# TMC2660-test-with-grbl2.net
KiCad netlist of a schematic drawn in EAGLE
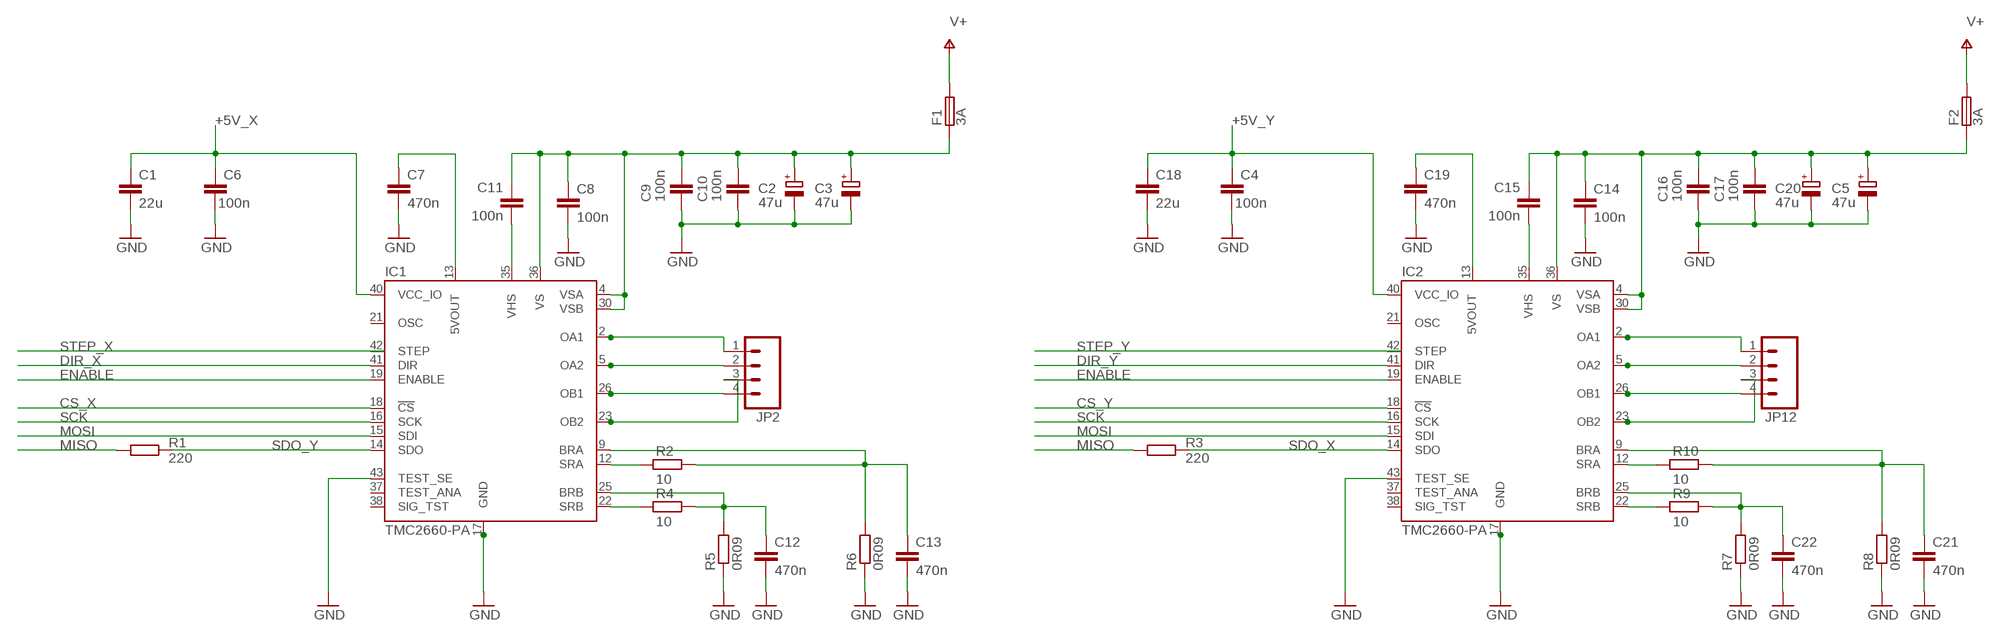
[diagram p0: schematic, sheet 1, part 1 of 2]
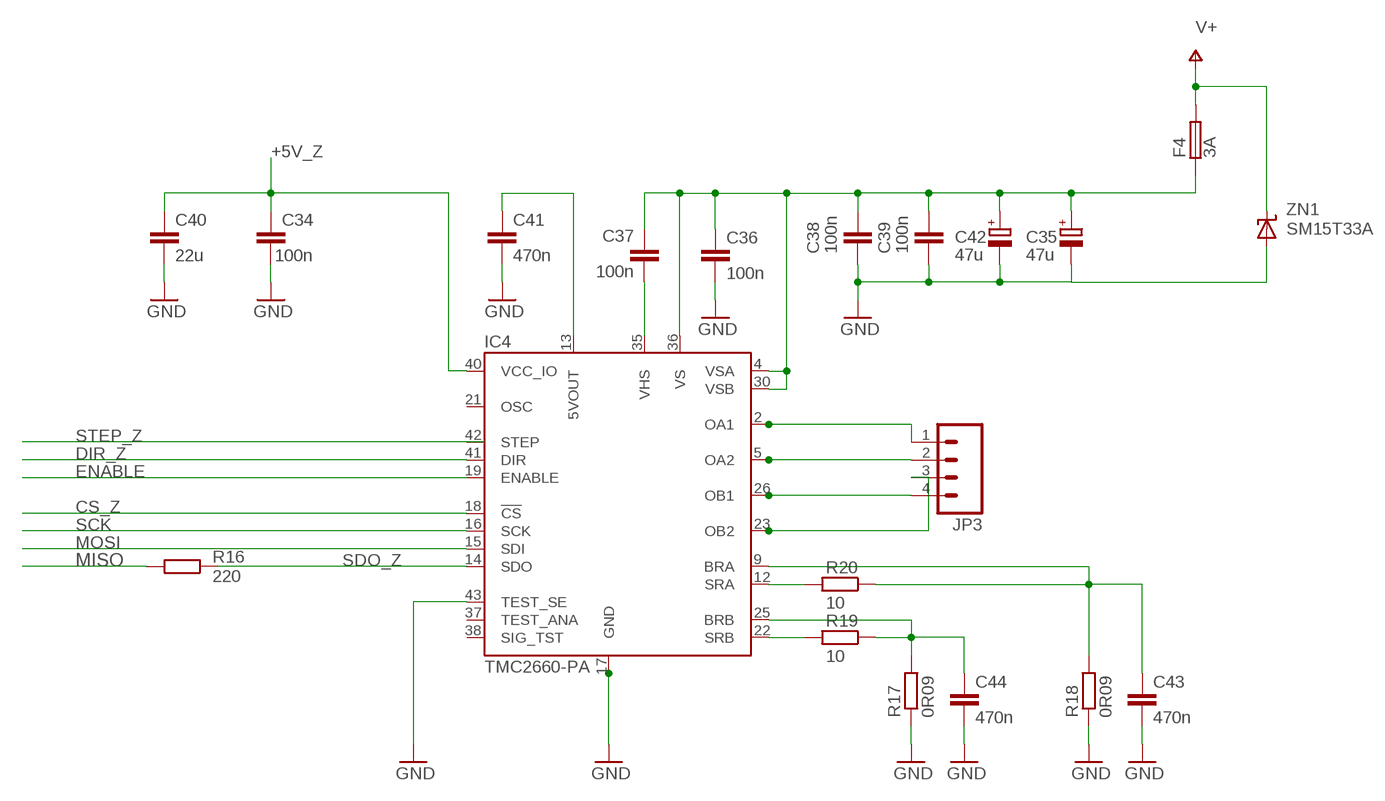
[diagram p1: schematic, sheet 1, part 2 of 2]
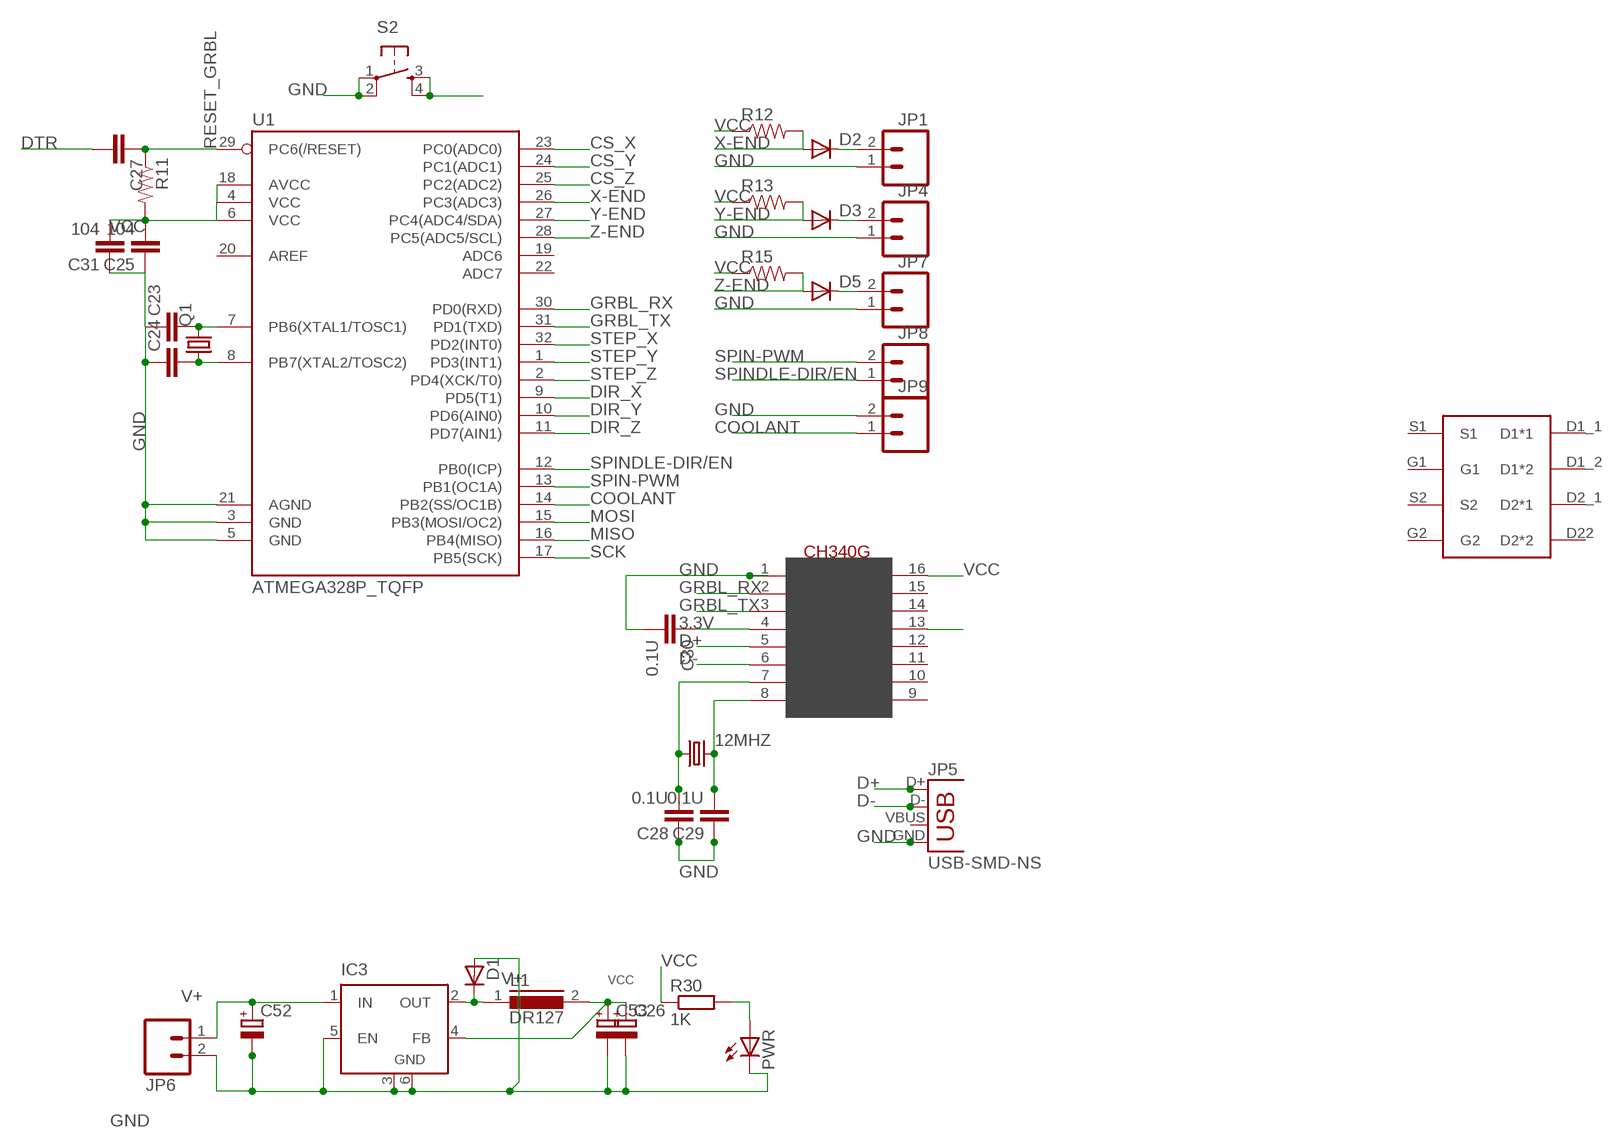
[diagram p2: schematic, sheet 2]

(export (version "E")
  (design (tool "Eeschema 10.0.6"))
  (components
    (comp (ref "12MHZ")
      (value "CRYSTALHC49UP")
      (footprint "eagle-import:HC49UP")
      (libsource (lib "eagle-import") (part "crystal_CRYSTALHC49UP"))
    )
    (comp (ref "C23")
      (value "CAP1206")
      (footprint "eagle-import:1206")
      (libsource (lib "eagle-import") (part "CAP1206"))
    )
    (comp (ref "C24")
      (value "CAP1206")
      (footprint "eagle-import:1206")
      (libsource (lib "eagle-import") (part "CAP1206"))
    )
    (comp (ref "C25")
      (value "104")
      (footprint "eagle-import:1206")
      (libsource (lib "eagle-import") (part "CAP1206"))
    )
    (comp (ref "C26")
      (value "CPOL-EUE2.5-6")
      (footprint "eagle-import:E2,5-6")
      (libsource (lib "eagle-import") (part "resistor_CPOL-EUE2.5-6"))
    )
    (comp (ref "C27")
      (value "CAP1206")
      (footprint "eagle-import:1206")
      (libsource (lib "eagle-import") (part "CAP1206"))
    )
    (comp (ref "C28")
      (value "0.1U")
      (footprint "eagle-import:C1206")
      (libsource (lib "eagle-import") (part "C-EUC1206"))
    )
    (comp (ref "C29")
      (value "0.1U")
      (footprint "eagle-import:C1206")
      (libsource (lib "eagle-import") (part "C-EUC1206"))
    )
    (comp (ref "C30")
      (value "0.1U")
      (footprint "eagle-import:C1206")
      (libsource (lib "eagle-import") (part "C-EUC1206"))
    )
    (comp (ref "C31")
      (value "104")
      (footprint "eagle-import:1206")
      (libsource (lib "eagle-import") (part "CAP1206"))
    )
    (comp (ref "C52")
      (value "CPOL-EUE5-8.5")
      (footprint "eagle-import:E5-8,5")
      (libsource (lib "eagle-import") (part "resistor_CPOL-EUE5-8.5"))
    )
    (comp (ref "C53")
      (value "CPOL-EUE5-8.5")
      (footprint "eagle-import:E5-8,5")
      (libsource (lib "eagle-import") (part "resistor_CPOL-EUE5-8.5"))
    )
    (comp (ref "D1")
      (value "D-SOD-80")
      (footprint "eagle-import:SOD80")
      (libsource (lib "eagle-import") (part "D-SOD-80"))
    )
    (comp (ref "D2")
      (value "DIODESMB")
      (footprint "eagle-import:SMB-DIODE")
      (libsource (lib "eagle-import") (part "DIODESMB"))
    )
    (comp (ref "D3")
      (value "DIODESMB")
      (footprint "eagle-import:SMB-DIODE")
      (libsource (lib "eagle-import") (part "DIODESMB"))
    )
    (comp (ref "D5")
      (value "DIODESMB")
      (footprint "eagle-import:SMB-DIODE")
      (libsource (lib "eagle-import") (part "DIODESMB"))
    )
    (comp (ref "IC3")
      (value "LM2596S")
      (footprint "eagle-import:TO263-5")
      (libsource (lib "eagle-import") (part "LM2596S"))
    )
    (comp (ref "JP1")
      (value "M023.5MM")
      (footprint "eagle-import:SCREWTERMINAL-3.5MM-2")
      (libsource (lib "eagle-import") (part "M023.5MM"))
    )
    (comp (ref "JP4")
      (value "M023.5MM")
      (footprint "eagle-import:SCREWTERMINAL-3.5MM-2")
      (libsource (lib "eagle-import") (part "M023.5MM"))
    )
    (comp (ref "JP5")
      (value "USB-SMD-NS")
      (footprint "eagle-import:USB-MINIB-NOSTOP")
      (libsource (lib "eagle-import") (part "USB-SMD-NS"))
    )
    (comp (ref "JP6")
      (value "M023.5MM")
      (footprint "eagle-import:SCREWTERMINAL-3.5MM-2")
      (libsource (lib "eagle-import") (part "M023.5MM"))
    )
    (comp (ref "JP7")
      (value "M023.5MM")
      (footprint "eagle-import:SCREWTERMINAL-3.5MM-2")
      (libsource (lib "eagle-import") (part "M023.5MM"))
    )
    (comp (ref "JP8")
      (value "M023.5MM")
      (footprint "eagle-import:SCREWTERMINAL-3.5MM-2")
      (libsource (lib "eagle-import") (part "M023.5MM"))
    )
    (comp (ref "JP9")
      (value "M023.5MM")
      (footprint "eagle-import:SCREWTERMINAL-3.5MM-2")
      (libsource (lib "eagle-import") (part "M023.5MM"))
    )
    (comp (ref "L1")
      (value "DR127")
      (footprint "eagle-import:DR127")
      (libsource (lib "eagle-import") (part "DR127"))
    )
    (comp (ref "PWR")
      (value "LEDCHIPLED_1206")
      (footprint "eagle-import:CHIPLED_1206")
      (libsource (lib "eagle-import") (part "LEDCHIPLED_1206"))
    )
    (comp (ref "Q1")
      (value "CRYSTALHC49UP")
      (footprint "eagle-import:HC49UP")
      (libsource (lib "eagle-import") (part "CRYSTALHC49UP"))
    )
    (comp (ref "R11")
      (value "RESISTOR1206")
      (footprint "eagle-import:1206")
      (libsource (lib "eagle-import") (part "RESISTOR1206"))
    )
    (comp (ref "R12")
      (value "RESISTOR1206")
      (footprint "eagle-import:1206")
      (libsource (lib "eagle-import") (part "RESISTOR1206"))
    )
    (comp (ref "R13")
      (value "RESISTOR1206")
      (footprint "eagle-import:1206")
      (libsource (lib "eagle-import") (part "RESISTOR1206"))
    )
    (comp (ref "R15")
      (value "RESISTOR1206")
      (footprint "eagle-import:1206")
      (libsource (lib "eagle-import") (part "RESISTOR1206"))
    )
    (comp (ref "R30")
      (value "1K")
      (footprint "eagle-import:M1206")
      (libsource (lib "eagle-import") (part "R-EU_M1206"))
    )
    (comp (ref "S2")
      (value "TAC_SWITCHSMD")
      (footprint "eagle-import:TACTILE_SWITCH_SMD")
      (libsource (lib "eagle-import") (part "TAC_SWITCHSMD"))
    )
    (comp (ref "U$3")
      (value "CSD88537ND")
      (footprint "eagle-import:CSD88537ND")
      (libsource (lib "eagle-import") (part "CSD88537ND"))
    )
    (comp (ref "U$4")
      (value "CH340G")
      (footprint "eagle-import:SOIC16")
      (libsource (lib "eagle-import") (part "CH340G"))
    )
    (comp (ref "U1")
      (value "ATMEGA328P_TQFP")
      (footprint "eagle-import:TQFP32-08")
      (libsource (lib "eagle-import") (part "ATMEGA328P_TQFP"))
    )
    (comp (ref "C1")
      (value "22u")
      (footprint "eagle-import:C1206")
      (fields (field (name "MANUFACTURER") "Taiyo Yuden") (field (name "VOLTAGE") "6.3V"))
      (libsource (lib "eagle-import") (part "C-EUC1206"))
    )
    (comp (ref "C2")
      (value "47u")
      (footprint "eagle-import:E5-8,5")
      (fields (field (name "MANUFACTURER") "PANASONIC") (field (name "VOLTAGE") "50V"))
      (libsource (lib "eagle-import") (part "CPOL-EUE5-8.5"))
    )
    (comp (ref "C3")
      (value "47u")
      (footprint "eagle-import:E5-8,5")
      (fields (field (name "MANUFACTURER") "PANASONIC") (field (name "VOLTAGE") "50V"))
      (libsource (lib "eagle-import") (part "CPOL-EUE5-8.5"))
    )
    (comp (ref "C4")
      (value "100n")
      (footprint "eagle-import:C1206K")
      (fields (field (name "MANUFACTURER") "Kemet") (field (name "VOLTAGE") "25V"))
      (libsource (lib "eagle-import") (part "C-EUC1206K"))
    )
    (comp (ref "C5")
      (value "47u")
      (footprint "eagle-import:E5-8,5")
      (fields (field (name "MANUFACTURER") "PANASONIC") (field (name "VOLTAGE") "50V"))
      (libsource (lib "eagle-import") (part "CPOL-EUE5-8.5"))
    )
    (comp (ref "C6")
      (value "100n")
      (footprint "eagle-import:C1206K")
      (fields (field (name "MANUFACTURER") "Kemet") (field (name "VOLTAGE") "25V"))
      (libsource (lib "eagle-import") (part "C-EUC1206K"))
    )
    (comp (ref "C7")
      (value "470n")
      (footprint "eagle-import:0805-WIDE")
      (fields (field (name "MANUFACTURER") "Vishay") (field (name "VOLTAGE") "10V"))
      (libsource (lib "eagle-import") (part "C-0805W"))
    )
    (comp (ref "C8")
      (value "100n")
      (footprint "eagle-import:C0603K")
      (fields (field (name "MANUFACTURER") "Kemet") (field (name "VOLTAGE") "50V"))
      (libsource (lib "eagle-import") (part "C-EUC0603K"))
    )
    (comp (ref "C9")
      (value "100n")
      (footprint "eagle-import:C0603K")
      (fields (field (name "MANUFACTURER") "Kemet") (field (name "VOLTAGE") "50V"))
      (libsource (lib "eagle-import") (part "C-EUC0603K"))
    )
    (comp (ref "C10")
      (value "100n")
      (footprint "eagle-import:C0603K")
      (fields (field (name "MANUFACTURER") "Kemet") (field (name "VOLTAGE") "50V"))
      (libsource (lib "eagle-import") (part "C-EUC0603K"))
    )
    (comp (ref "C11")
      (value "100n")
      (footprint "eagle-import:C0603K")
      (fields (field (name "MANUFACTURER") "Kemet") (field (name "VOLTAGE") "50V"))
      (libsource (lib "eagle-import") (part "C-EUC0603K"))
    )
    (comp (ref "C12")
      (value "470n")
      (footprint "eagle-import:0805-WIDE")
      (fields (field (name "MANUFACTURER") "Vishay") (field (name "VOLTAGE") "10V"))
      (libsource (lib "eagle-import") (part "C-0805W"))
    )
    (comp (ref "C13")
      (value "470n")
      (footprint "eagle-import:0805-WIDE")
      (fields (field (name "MANUFACTURER") "Vishay") (field (name "VOLTAGE") "10V"))
      (libsource (lib "eagle-import") (part "C-0805W"))
    )
    (comp (ref "C14")
      (value "100n")
      (footprint "eagle-import:C0603K")
      (fields (field (name "MANUFACTURER") "Kemet") (field (name "VOLTAGE") "50V"))
      (libsource (lib "eagle-import") (part "C-EUC0603K"))
    )
    (comp (ref "C15")
      (value "100n")
      (footprint "eagle-import:C0603K")
      (fields (field (name "MANUFACTURER") "Kemet") (field (name "VOLTAGE") "50V"))
      (libsource (lib "eagle-import") (part "C-EUC0603K"))
    )
    (comp (ref "C16")
      (value "100n")
      (footprint "eagle-import:C0603K")
      (fields (field (name "MANUFACTURER") "Kemet") (field (name "VOLTAGE") "50V"))
      (libsource (lib "eagle-import") (part "C-EUC0603K"))
    )
    (comp (ref "C17")
      (value "100n")
      (footprint "eagle-import:C0603K")
      (fields (field (name "MANUFACTURER") "Kemet") (field (name "VOLTAGE") "50V"))
      (libsource (lib "eagle-import") (part "C-EUC0603K"))
    )
    (comp (ref "C18")
      (value "22u")
      (footprint "eagle-import:C1206")
      (fields (field (name "MANUFACTURER") "Taiyo Yuden") (field (name "VOLTAGE") "6.3V"))
      (libsource (lib "eagle-import") (part "C-EUC1206"))
    )
    (comp (ref "C19")
      (value "470n")
      (footprint "eagle-import:0805-WIDE")
      (fields (field (name "MANUFACTURER") "Vishay") (field (name "VOLTAGE") "10V"))
      (libsource (lib "eagle-import") (part "C-0805W"))
    )
    (comp (ref "C20")
      (value "47u")
      (footprint "eagle-import:E5-8,5")
      (fields (field (name "MANUFACTURER") "PANASONIC") (field (name "VOLTAGE") "50V"))
      (libsource (lib "eagle-import") (part "CPOL-EUE5-8.5"))
    )
    (comp (ref "C21")
      (value "470n")
      (footprint "eagle-import:0805-WIDE")
      (fields (field (name "MANUFACTURER") "Vishay") (field (name "VOLTAGE") "10V"))
      (libsource (lib "eagle-import") (part "C-0805W"))
    )
    (comp (ref "C22")
      (value "470n")
      (footprint "eagle-import:0805-WIDE")
      (fields (field (name "MANUFACTURER") "Vishay") (field (name "VOLTAGE") "10V"))
      (libsource (lib "eagle-import") (part "C-0805W"))
    )
    (comp (ref "C34")
      (value "100n")
      (footprint "eagle-import:C1206K")
      (fields (field (name "MANUFACTURER") "Kemet") (field (name "VOLTAGE") "25V"))
      (libsource (lib "eagle-import") (part "C-EUC1206K"))
    )
    (comp (ref "C35")
      (value "47u")
      (footprint "eagle-import:E5-8,5")
      (fields (field (name "MANUFACTURER") "PANASONIC") (field (name "VOLTAGE") "50V"))
      (libsource (lib "eagle-import") (part "CPOL-EUE5-8.5"))
    )
    (comp (ref "C36")
      (value "100n")
      (footprint "eagle-import:C0603K")
      (fields (field (name "MANUFACTURER") "Kemet") (field (name "VOLTAGE") "50V"))
      (libsource (lib "eagle-import") (part "C-EUC0603K"))
    )
    (comp (ref "C37")
      (value "100n")
      (footprint "eagle-import:C0603K")
      (fields (field (name "MANUFACTURER") "Kemet") (field (name "VOLTAGE") "50V"))
      (libsource (lib "eagle-import") (part "C-EUC0603K"))
    )
    (comp (ref "C38")
      (value "100n")
      (footprint "eagle-import:C0603K")
      (fields (field (name "MANUFACTURER") "Kemet") (field (name "VOLTAGE") "50V"))
      (libsource (lib "eagle-import") (part "C-EUC0603K"))
    )
    (comp (ref "C39")
      (value "100n")
      (footprint "eagle-import:C0603K")
      (fields (field (name "MANUFACTURER") "Kemet") (field (name "VOLTAGE") "50V"))
      (libsource (lib "eagle-import") (part "C-EUC0603K"))
    )
    (comp (ref "C40")
      (value "22u")
      (footprint "eagle-import:C1206")
      (fields (field (name "MANUFACTURER") "Taiyo Yuden") (field (name "VOLTAGE") "6.3V"))
      (libsource (lib "eagle-import") (part "C-EUC1206"))
    )
    (comp (ref "C41")
      (value "470n")
      (footprint "eagle-import:0805-WIDE")
      (fields (field (name "MANUFACTURER") "Vishay") (field (name "VOLTAGE") "10V"))
      (libsource (lib "eagle-import") (part "C-0805W"))
    )
    (comp (ref "C42")
      (value "47u")
      (footprint "eagle-import:E5-8,5")
      (fields (field (name "MANUFACTURER") "PANASONIC") (field (name "VOLTAGE") "50V"))
      (libsource (lib "eagle-import") (part "CPOL-EUE5-8.5"))
    )
    (comp (ref "C43")
      (value "470n")
      (footprint "eagle-import:0805-WIDE")
      (fields (field (name "MANUFACTURER") "Vishay") (field (name "VOLTAGE") "10V"))
      (libsource (lib "eagle-import") (part "C-0805W"))
    )
    (comp (ref "C44")
      (value "470n")
      (footprint "eagle-import:0805-WIDE")
      (fields (field (name "MANUFACTURER") "Vishay") (field (name "VOLTAGE") "10V"))
      (libsource (lib "eagle-import") (part "C-0805W"))
    )
    (comp (ref "F1")
      (value "3A")
      (footprint "eagle-import:AF2")
      (fields
        (field (name "MANUFACTURER") "AEM")
        (field (name "MANUFACTURER_1") "Cooper Bussman")
        (field (name "PARTNR") "CB61F3A-TR2")
        (field (name "VOLTAGE") "125V")
      )
      (libsource (lib "eagle-import") (part "AF2-FUSE_AF"))
    )
    (comp (ref "F2")
      (value "3A")
      (footprint "eagle-import:AF2")
      (fields
        (field (name "MANUFACTURER") "AEM")
        (field (name "MANUFACTURER_1") "Cooper Bussman")
        (field (name "PARTNR") "CB61F3A-TR2")
        (field (name "VOLTAGE") "125V")
      )
      (libsource (lib "eagle-import") (part "AF2-FUSE_AF"))
    )
    (comp (ref "F4")
      (value "3A")
      (footprint "eagle-import:AF2")
      (fields
        (field (name "MANUFACTURER") "AEM")
        (field (name "MANUFACTURER_1") "Cooper Bussman")
        (field (name "PARTNR") "CB61F3A-TR2")
        (field (name "VOLTAGE") "125V")
      )
      (libsource (lib "eagle-import") (part "AF2-FUSE_AF"))
    )
    (comp (ref "IC1")
      (value "TMC2660-PA")
      (footprint "eagle-import:PQFP44")
      (fields (field (name "MANUFACTURER") "TRINAMIC"))
      (libsource (lib "eagle-import") (part "TMC2660-PA"))
    )
    (comp (ref "IC2")
      (value "TMC2660-PA")
      (footprint "eagle-import:PQFP44")
      (fields (field (name "MANUFACTURER") "TRINAMIC"))
      (libsource (lib "eagle-import") (part "TMC2660-PA"))
    )
    (comp (ref "IC4")
      (value "TMC2660-PA")
      (footprint "eagle-import:PQFP44")
      (fields (field (name "MANUFACTURER") "TRINAMIC"))
      (libsource (lib "eagle-import") (part "TMC2660-PA"))
    )
    (comp (ref "JP2")
      (value "M04SCREW")
      (footprint "eagle-import:SCREWTERMINAL-3.5MM-4")
      (libsource (lib "eagle-import") (part "M04SCREW"))
    )
    (comp (ref "JP3")
      (value "M04SCREW")
      (footprint "eagle-import:SCREWTERMINAL-3.5MM-4")
      (libsource (lib "eagle-import") (part "M04SCREW"))
    )
    (comp (ref "JP12")
      (value "M04SCREW")
      (footprint "eagle-import:SCREWTERMINAL-3.5MM-4")
      (libsource (lib "eagle-import") (part "M04SCREW"))
    )
    (comp (ref "R1")
      (value "220")
      (footprint "eagle-import:R0603")
      (fields (field (name "MANUFACTURER") "KOA Speer"))
      (libsource (lib "eagle-import") (part "R-EU_R0603"))
    )
    (comp (ref "R2")
      (value "10")
      (footprint "eagle-import:R0603")
      (fields (field (name "MANUFACTURER") "KOA Speer"))
      (libsource (lib "eagle-import") (part "R-EU_R0603"))
    )
    (comp (ref "R3")
      (value "220")
      (footprint "eagle-import:R0603")
      (fields (field (name "MANUFACTURER") "KOA Speer"))
      (libsource (lib "eagle-import") (part "R-EU_R0603"))
    )
    (comp (ref "R4")
      (value "10")
      (footprint "eagle-import:R0603")
      (fields (field (name "MANUFACTURER") "KOA Speer"))
      (libsource (lib "eagle-import") (part "R-EU_R0603"))
    )
    (comp (ref "R5")
      (value "0R09")
      (footprint "eagle-import:R1206")
      (fields (field (name "MANUFACTURER") "Panasonic") (field (name "POWER") "0.75W"))
      (libsource (lib "eagle-import") (part "R-EU_R1206"))
    )
    (comp (ref "R6")
      (value "0R09")
      (footprint "eagle-import:R1206")
      (fields (field (name "MANUFACTURER") "Panasonic") (field (name "POWER") "0.75W"))
      (libsource (lib "eagle-import") (part "R-EU_R1206"))
    )
    (comp (ref "R7")
      (value "0R09")
      (footprint "eagle-import:R1206")
      (fields (field (name "MANUFACTURER") "Panasonic") (field (name "POWER") "0.75W"))
      (libsource (lib "eagle-import") (part "R-EU_R1206"))
    )
    (comp (ref "R8")
      (value "0R09")
      (footprint "eagle-import:R1206")
      (fields (field (name "MANUFACTURER") "Panasonic") (field (name "POWER") "0.75W"))
      (libsource (lib "eagle-import") (part "R-EU_R1206"))
    )
    (comp (ref "R9")
      (value "10")
      (footprint "eagle-import:R0603")
      (fields (field (name "MANUFACTURER") "KOA Speer"))
      (libsource (lib "eagle-import") (part "R-EU_R0603"))
    )
    (comp (ref "R10")
      (value "10")
      (footprint "eagle-import:R0603")
      (fields (field (name "MANUFACTURER") "KOA Speer"))
      (libsource (lib "eagle-import") (part "R-EU_R0603"))
    )
    (comp (ref "R16")
      (value "220")
      (footprint "eagle-import:R0603")
      (fields (field (name "MANUFACTURER") "KOA Speer"))
      (libsource (lib "eagle-import") (part "R-EU_R0603"))
    )
    (comp (ref "R17")
      (value "0R09")
      (footprint "eagle-import:R1206")
      (fields (field (name "MANUFACTURER") "Panasonic") (field (name "POWER") "0.75W"))
      (libsource (lib "eagle-import") (part "R-EU_R1206"))
    )
    (comp (ref "R18")
      (value "0R09")
      (footprint "eagle-import:R1206")
      (fields (field (name "MANUFACTURER") "Panasonic") (field (name "POWER") "0.75W"))
      (libsource (lib "eagle-import") (part "R-EU_R1206"))
    )
    (comp (ref "R19")
      (value "10")
      (footprint "eagle-import:R0603")
      (fields (field (name "MANUFACTURER") "KOA Speer"))
      (libsource (lib "eagle-import") (part "R-EU_R0603"))
    )
    (comp (ref "R20")
      (value "10")
      (footprint "eagle-import:R0603")
      (fields (field (name "MANUFACTURER") "KOA Speer"))
      (libsource (lib "eagle-import") (part "R-EU_R0603"))
    )
    (comp (ref "ZN1")
      (value "SM15T33A")
      (footprint "eagle-import:SMC")
      (fields (field (name "MANUFACTURER") "ST"))
      (libsource (lib "eagle-import") (part "D-ZN_SMC"))
    )
  )
  (nets
    (net (code "1") (name "+5V_X") (class "Default")
      (node (ref "C1") (pin "1") (pinfunction "1_1") (pintype "passive"))
      (node (ref "C6") (pin "2") (pinfunction "2_2") (pintype "passive"))
      (node (ref "IC1") (pin "40") (pinfunction "VCC_IO_40") (pintype "bidirectional"))
    )
    (net (code "2") (name "+5V_Y") (class "Default")
      (node (ref "C18") (pin "1") (pinfunction "1_1") (pintype "passive"))
      (node (ref "C4") (pin "2") (pinfunction "2_2") (pintype "passive"))
      (node (ref "IC2") (pin "40") (pinfunction "VCC_IO_40") (pintype "bidirectional"))
    )
    (net (code "3") (name "+5V_Z") (class "Default")
      (node (ref "C34") (pin "2") (pinfunction "2_2") (pintype "passive"))
      (node (ref "C40") (pin "1") (pinfunction "1_1") (pintype "passive"))
      (node (ref "IC4") (pin "40") (pinfunction "VCC_IO_40") (pintype "bidirectional"))
    )
    (net (code "4") (name "3.3V") (class "Default")
      (node (ref "C30") (pin "1") (pinfunction "1_1") (pintype "passive"))
      (node (ref "U$4") (pin "4") (pinfunction "V3_4") (pintype "bidirectional"))
    )
    (net (code "5") (name "COOLANT") (class "Default")
      (node (ref "JP9") (pin "1") (pinfunction "1_1") (pintype "passive"))
      (node (ref "U1") (pin "14") (pinfunction "PB2(SS/OC1B)_14") (pintype "bidirectional"))
    )
    (net (code "6") (name "CS_X") (class "Default")
      (node (ref "IC1") (pin "18") (pinfunction "~{CS}_18") (pintype "bidirectional"))
      (node (ref "U1") (pin "23") (pinfunction "PC0(ADC0)_23") (pintype "bidirectional"))
    )
    (net (code "7") (name "CS_Y") (class "Default")
      (node (ref "IC2") (pin "18") (pinfunction "~{CS}_18") (pintype "bidirectional"))
      (node (ref "U1") (pin "24") (pinfunction "PC1(ADC1)_24") (pintype "bidirectional"))
    )
    (net (code "8") (name "CS_Z") (class "Default")
      (node (ref "IC4") (pin "18") (pinfunction "~{CS}_18") (pintype "bidirectional"))
      (node (ref "U1") (pin "25") (pinfunction "PC2(ADC2)_25") (pintype "bidirectional"))
    )
    (net (code "9") (name "D+") (class "Default")
      (node (ref "JP5") (pin "D+") (pinfunction "D+_D+") (pintype "bidirectional"))
      (node (ref "U$4") (pin "5") (pinfunction "D+_5") (pintype "bidirectional"))
    )
    (net (code "10") (name "D-") (class "Default")
      (node (ref "JP5") (pin "D-") (pinfunction "D-_D-") (pintype "bidirectional"))
      (node (ref "U$4") (pin "6") (pinfunction "D-_6") (pintype "bidirectional"))
    )
    (net (code "11") (name "D1*1") (class "Default")
      (node (ref "U$3") (pin "D1_1") (pinfunction "D1*1_D1_1") (pintype "power_in"))
    )
    (net (code "12") (name "D1*2") (class "Default")
      (node (ref "U$3") (pin "D1_2") (pinfunction "D1*2_D1_2") (pintype "power_in"))
    )
    (net (code "13") (name "D2*1") (class "Default")
      (node (ref "U$3") (pin "D2_1") (pinfunction "D2*1_D2_1") (pintype "power_in"))
    )
    (net (code "14") (name "D2*2") (class "Default")
      (node (ref "U$3") (pin "D22") (pinfunction "D2*2_D22") (pintype "power_in"))
    )
    (net (code "15") (name "DIR_X") (class "Default")
      (node (ref "IC1") (pin "41") (pinfunction "DIR_41") (pintype "bidirectional"))
      (node (ref "U1") (pin "9") (pinfunction "PD5(T1)_9") (pintype "bidirectional"))
    )
    (net (code "16") (name "DIR_Y") (class "Default")
      (node (ref "IC2") (pin "41") (pinfunction "DIR_41") (pintype "bidirectional"))
      (node (ref "U1") (pin "10") (pinfunction "PD6(AIN0)_10") (pintype "bidirectional"))
    )
    (net (code "17") (name "DIR_Z") (class "Default")
      (node (ref "IC4") (pin "41") (pinfunction "DIR_41") (pintype "bidirectional"))
      (node (ref "U1") (pin "11") (pinfunction "PD7(AIN1)_11") (pintype "bidirectional"))
    )
    (net (code "18") (name "DTR") (class "Default")
      (node (ref "C27") (pin "2") (pinfunction "2_2") (pintype "passive"))
      (node (ref "U$4") (pin "13") (pinfunction "DTR_13") (pintype "bidirectional"))
    )
    (net (code "19") (name "ENABLE") (class "Default")
      (node (ref "IC1") (pin "19") (pinfunction "ENABLE_19") (pintype "bidirectional"))
      (node (ref "IC2") (pin "19") (pinfunction "ENABLE_19") (pintype "bidirectional"))
      (node (ref "IC4") (pin "19") (pinfunction "ENABLE_19") (pintype "bidirectional"))
    )
    (net (code "20") (name "G1") (class "Default")
      (node (ref "U$3") (pin "G1") (pinfunction "G1_G1") (pintype "power_in"))
    )
    (net (code "21") (name "G2") (class "Default")
      (node (ref "U$3") (pin "G2") (pinfunction "G2_G2") (pintype "power_in"))
    )
    (net (code "22") (name "GND") (class "Default")
      (node (ref "C1") (pin "2") (pinfunction "2_2") (pintype "passive"))
      (node (ref "C10") (pin "1") (pinfunction "1_1") (pintype "passive"))
      (node (ref "C12") (pin "2") (pinfunction "2_2") (pintype "passive"))
      (node (ref "C13") (pin "2") (pinfunction "2_2") (pintype "passive"))
      (node (ref "C14") (pin "2") (pinfunction "2_2") (pintype "passive"))
      (node (ref "C16") (pin "1") (pinfunction "1_1") (pintype "passive"))
      (node (ref "C17") (pin "1") (pinfunction "1_1") (pintype "passive"))
      (node (ref "C18") (pin "2") (pinfunction "2_2") (pintype "passive"))
      (node (ref "C19") (pin "2") (pinfunction "2_2") (pintype "passive"))
      (node (ref "C2") (pin "-") (pinfunction "-_-") (pintype "passive"))
      (node (ref "C20") (pin "-") (pinfunction "-_-") (pintype "passive"))
      (node (ref "C21") (pin "2") (pinfunction "2_2") (pintype "passive"))
      (node (ref "C22") (pin "2") (pinfunction "2_2") (pintype "passive"))
      (node (ref "C23") (pin "1") (pinfunction "1_1") (pintype "passive"))
      (node (ref "C24") (pin "1") (pinfunction "1_1") (pintype "passive"))
      (node (ref "C25") (pin "1") (pinfunction "1_1") (pintype "passive"))
      (node (ref "C26") (pin "-") (pinfunction "-_-") (pintype "passive"))
      (node (ref "C28") (pin "1") (pinfunction "1_1") (pintype "passive"))
      (node (ref "C29") (pin "1") (pinfunction "1_1") (pintype "passive"))
      (node (ref "C3") (pin "-") (pinfunction "-_-") (pintype "passive"))
      (node (ref "C30") (pin "2") (pinfunction "2_2") (pintype "passive"))
      (node (ref "C31") (pin "1") (pinfunction "1_1") (pintype "passive"))
      (node (ref "C34") (pin "1") (pinfunction "1_1") (pintype "passive"))
      (node (ref "C35") (pin "-") (pinfunction "-_-") (pintype "passive"))
      (node (ref "C36") (pin "2") (pinfunction "2_2") (pintype "passive"))
      (node (ref "C38") (pin "1") (pinfunction "1_1") (pintype "passive"))
      (node (ref "C39") (pin "1") (pinfunction "1_1") (pintype "passive"))
      (node (ref "C4") (pin "1") (pinfunction "1_1") (pintype "passive"))
      (node (ref "C40") (pin "2") (pinfunction "2_2") (pintype "passive"))
      (node (ref "C41") (pin "2") (pinfunction "2_2") (pintype "passive"))
      (node (ref "C42") (pin "-") (pinfunction "-_-") (pintype "passive"))
      (node (ref "C43") (pin "2") (pinfunction "2_2") (pintype "passive"))
      (node (ref "C44") (pin "2") (pinfunction "2_2") (pintype "passive"))
      (node (ref "C5") (pin "-") (pinfunction "-_-") (pintype "passive"))
      (node (ref "C52") (pin "-") (pinfunction "-_-") (pintype "passive"))
      (node (ref "C53") (pin "-") (pinfunction "-_-") (pintype "passive"))
      (node (ref "C6") (pin "1") (pinfunction "1_1") (pintype "passive"))
      (node (ref "C7") (pin "2") (pinfunction "2_2") (pintype "passive"))
      (node (ref "C8") (pin "2") (pinfunction "2_2") (pintype "passive"))
      (node (ref "C9") (pin "1") (pinfunction "1_1") (pintype "passive"))
      (node (ref "D1") (pin "2") (pinfunction "A_2") (pintype "passive"))
      (node (ref "IC1") (pin "17") (pinfunction "GND_17") (pintype "bidirectional"))
      (node (ref "IC1") (pin "39") (pinfunction "GND1_39") (pintype "bidirectional"))
      (node (ref "IC1") (pin "43") (pinfunction "TEST_SE_43") (pintype "bidirectional"))
      (node (ref "IC1") (pin "44") (pinfunction "GND2_44") (pintype "bidirectional"))
      (node (ref "IC2") (pin "17") (pinfunction "GND_17") (pintype "bidirectional"))
      (node (ref "IC2") (pin "39") (pinfunction "GND1_39") (pintype "bidirectional"))
      (node (ref "IC2") (pin "43") (pinfunction "TEST_SE_43") (pintype "bidirectional"))
      (node (ref "IC2") (pin "44") (pinfunction "GND2_44") (pintype "bidirectional"))
      (node (ref "IC3") (pin "3") (pinfunction "GND_3") (pintype "power_in"))
      (node (ref "IC3") (pin "5") (pinfunction "EN_5") (pintype "input"))
      (node (ref "IC3") (pin "6") (pinfunction "GND_6") (pintype "power_in"))
      (node (ref "IC4") (pin "17") (pinfunction "GND_17") (pintype "bidirectional"))
      (node (ref "IC4") (pin "39") (pinfunction "GND1_39") (pintype "bidirectional"))
      (node (ref "IC4") (pin "43") (pinfunction "TEST_SE_43") (pintype "bidirectional"))
      (node (ref "IC4") (pin "44") (pinfunction "GND2_44") (pintype "bidirectional"))
      (node (ref "JP1") (pin "1") (pinfunction "1_1") (pintype "passive"))
      (node (ref "JP4") (pin "1") (pinfunction "1_1") (pintype "passive"))
      (node (ref "JP5") (pin "GND") (pinfunction "GND_GND") (pintype "bidirectional"))
      (node (ref "JP6") (pin "2") (pinfunction "2_2") (pintype "passive"))
      (node (ref "JP7") (pin "1") (pinfunction "1_1") (pintype "passive"))
      (node (ref "JP9") (pin "2") (pinfunction "2_2") (pintype "passive"))
      (node (ref "PWR") (pin "C") (pinfunction "C_C") (pintype "passive"))
      (node (ref "R17") (pin "1") (pinfunction "1_1") (pintype "passive"))
      (node (ref "R18") (pin "1") (pinfunction "1_1") (pintype "passive"))
      (node (ref "R5") (pin "1") (pinfunction "1_1") (pintype "passive"))
      (node (ref "R6") (pin "1") (pinfunction "1_1") (pintype "passive"))
      (node (ref "R7") (pin "1") (pinfunction "1_1") (pintype "passive"))
      (node (ref "R8") (pin "1") (pinfunction "1_1") (pintype "passive"))
      (node (ref "S2") (pin "1") (pinfunction "1_1") (pintype "passive"))
      (node (ref "S2") (pin "2") (pinfunction "2_2") (pintype "passive"))
      (node (ref "U$4") (pin "1") (pinfunction "GND_1") (pintype "bidirectional"))
      (node (ref "U1") (pin "21") (pinfunction "AGND_21") (pintype "bidirectional"))
      (node (ref "U1") (pin "3") (pinfunction "GND_3") (pintype "bidirectional"))
      (node (ref "U1") (pin "5") (pinfunction "GND_5") (pintype "bidirectional"))
      (node (ref "ZN1") (pin "P$2") (pinfunction "A_P$2") (pintype "passive"))
    )
    (net (code "23") (name "GRBL_RX") (class "Default")
      (node (ref "U$4") (pin "2") (pinfunction "TX_2") (pintype "bidirectional"))
      (node (ref "U1") (pin "30") (pinfunction "PD0(RXD)_30") (pintype "bidirectional"))
    )
    (net (code "24") (name "GRBL_TX") (class "Default")
      (node (ref "U$4") (pin "3") (pinfunction "RX_3") (pintype "bidirectional"))
      (node (ref "U1") (pin "31") (pinfunction "PD1(TXD)_31") (pintype "bidirectional"))
    )
    (net (code "25") (name "MISO") (class "Default")
      (node (ref "R1") (pin "2") (pinfunction "2_2") (pintype "passive"))
      (node (ref "R16") (pin "2") (pinfunction "2_2") (pintype "passive"))
      (node (ref "R3") (pin "2") (pinfunction "2_2") (pintype "passive"))
      (node (ref "U1") (pin "16") (pinfunction "PB4(MISO)_16") (pintype "bidirectional"))
    )
    (net (code "26") (name "MOSI") (class "Default")
      (node (ref "IC1") (pin "15") (pinfunction "SDI_15") (pintype "bidirectional"))
      (node (ref "IC2") (pin "15") (pinfunction "SDI_15") (pintype "bidirectional"))
      (node (ref "IC4") (pin "15") (pinfunction "SDI_15") (pintype "bidirectional"))
      (node (ref "U1") (pin "15") (pinfunction "PB3(MOSI/OC2)_15") (pintype "bidirectional"))
    )
    (net (code "27") (name "Net-(D1-C)") (class "Default")
      (node (ref "D1") (pin "1") (pinfunction "C_1") (pintype "passive"))
      (node (ref "IC3") (pin "2") (pinfunction "OUT_2") (pintype "output"))
      (node (ref "L1") (pin "1") (pinfunction "1_1") (pintype "passive"))
    )
    (net (code "28") (name "Net-(D2-PadC)") (class "Default")
      (node (ref "D2") (pin "C") (pinfunction "C_C") (pintype "passive"))
      (node (ref "JP1") (pin "2") (pinfunction "2_2") (pintype "passive"))
    )
    (net (code "29") (name "Net-(D3-PadC)") (class "Default")
      (node (ref "D3") (pin "C") (pinfunction "C_C") (pintype "passive"))
      (node (ref "JP4") (pin "2") (pinfunction "2_2") (pintype "passive"))
    )
    (net (code "30") (name "Net-(D5-PadC)") (class "Default")
      (node (ref "D5") (pin "C") (pinfunction "C_C") (pintype "passive"))
      (node (ref "JP7") (pin "2") (pinfunction "2_2") (pintype "passive"))
    )
    (net (code "31") (name "Net-(F1-1)") (class "Default")
      (node (ref "C10") (pin "2") (pinfunction "2_2") (pintype "passive"))
      (node (ref "C11") (pin "2") (pinfunction "2_2") (pintype "passive"))
      (node (ref "C2") (pin "+") (pinfunction "+_+") (pintype "passive"))
      (node (ref "C3") (pin "+") (pinfunction "+_+") (pintype "passive"))
      (node (ref "C8") (pin "1") (pinfunction "1_1") (pintype "passive"))
      (node (ref "C9") (pin "2") (pinfunction "2_2") (pintype "passive"))
      (node (ref "F1") (pin "P$1") (pinfunction "1_P$1") (pintype "passive"))
      (node (ref "IC1") (pin "30") (pinfunction "VSB_30") (pintype "bidirectional"))
      (node (ref "IC1") (pin "36") (pinfunction "VS_36") (pintype "bidirectional"))
      (node (ref "IC1") (pin "4") (pinfunction "VSA_4") (pintype "bidirectional"))
    )
    (net (code "32") (name "Net-(F2-1)") (class "Default")
      (node (ref "C14") (pin "1") (pinfunction "1_1") (pintype "passive"))
      (node (ref "C15") (pin "2") (pinfunction "2_2") (pintype "passive"))
      (node (ref "C16") (pin "2") (pinfunction "2_2") (pintype "passive"))
      (node (ref "C17") (pin "2") (pinfunction "2_2") (pintype "passive"))
      (node (ref "C20") (pin "+") (pinfunction "+_+") (pintype "passive"))
      (node (ref "C5") (pin "+") (pinfunction "+_+") (pintype "passive"))
      (node (ref "F2") (pin "P$1") (pinfunction "1_P$1") (pintype "passive"))
      (node (ref "IC2") (pin "30") (pinfunction "VSB_30") (pintype "bidirectional"))
      (node (ref "IC2") (pin "36") (pinfunction "VS_36") (pintype "bidirectional"))
      (node (ref "IC2") (pin "4") (pinfunction "VSA_4") (pintype "bidirectional"))
    )
    (net (code "33") (name "Net-(F4-1)") (class "Default")
      (node (ref "C35") (pin "+") (pinfunction "+_+") (pintype "passive"))
      (node (ref "C36") (pin "1") (pinfunction "1_1") (pintype "passive"))
      (node (ref "C37") (pin "2") (pinfunction "2_2") (pintype "passive"))
      (node (ref "C38") (pin "2") (pinfunction "2_2") (pintype "passive"))
      (node (ref "C39") (pin "2") (pinfunction "2_2") (pintype "passive"))
      (node (ref "C42") (pin "+") (pinfunction "+_+") (pintype "passive"))
      (node (ref "F4") (pin "P$1") (pinfunction "1_P$1") (pintype "passive"))
      (node (ref "IC4") (pin "30") (pinfunction "VSB_30") (pintype "bidirectional"))
      (node (ref "IC4") (pin "36") (pinfunction "VS_36") (pintype "bidirectional"))
      (node (ref "IC4") (pin "4") (pinfunction "VSA_4") (pintype "bidirectional"))
    )
    (net (code "34") (name "Net-(IC1-5VOUT)") (class "Default")
      (node (ref "C7") (pin "1") (pinfunction "1_1") (pintype "passive"))
      (node (ref "IC1") (pin "13") (pinfunction "5VOUT_13") (pintype "bidirectional"))
    )
    (net (code "35") (name "Net-(IC1-BRA)") (class "Default")
      (node (ref "C13") (pin "1") (pinfunction "1_1") (pintype "passive"))
      (node (ref "IC1") (pin "9") (pinfunction "BRA_9") (pintype "bidirectional"))
      (node (ref "R2") (pin "1") (pinfunction "1_1") (pintype "passive"))
      (node (ref "R6") (pin "2") (pinfunction "2_2") (pintype "passive"))
    )
    (net (code "36") (name "Net-(IC1-BRB)") (class "Default")
      (node (ref "C12") (pin "1") (pinfunction "1_1") (pintype "passive"))
      (node (ref "IC1") (pin "25") (pinfunction "BRB_25") (pintype "bidirectional"))
      (node (ref "R4") (pin "1") (pinfunction "1_1") (pintype "passive"))
      (node (ref "R5") (pin "2") (pinfunction "2_2") (pintype "passive"))
    )
    (net (code "37") (name "Net-(IC1-OA1)") (class "Default")
      (node (ref "IC1") (pin "2") (pinfunction "OA1_2") (pintype "bidirectional"))
      (node (ref "IC1") (pin "3") (pinfunction "OA1_1_3") (pintype "bidirectional"))
      (node (ref "IC1") (pin "7") (pinfunction "OA1_2_7") (pintype "bidirectional"))
      (node (ref "IC1") (pin "8") (pinfunction "OA1_3_8") (pintype "bidirectional"))
      (node (ref "JP2") (pin "1") (pinfunction "1_1") (pintype "passive"))
    )
    (net (code "38") (name "Net-(IC1-OA2)") (class "Default")
      (node (ref "IC1") (pin "10") (pinfunction "OA2_2_10") (pintype "bidirectional"))
      (node (ref "IC1") (pin "11") (pinfunction "OA2_3_11") (pintype "bidirectional"))
      (node (ref "IC1") (pin "5") (pinfunction "OA2_5") (pintype "bidirectional"))
      (node (ref "IC1") (pin "6") (pinfunction "OA2_1_6") (pintype "bidirectional"))
      (node (ref "JP2") (pin "2") (pinfunction "2_2") (pintype "passive"))
    )
    (net (code "39") (name "Net-(IC1-OB1)") (class "Default")
      (node (ref "IC1") (pin "26") (pinfunction "OB1_26") (pintype "bidirectional"))
      (node (ref "IC1") (pin "27") (pinfunction "OB1_1_27") (pintype "bidirectional"))
      (node (ref "IC1") (pin "31") (pinfunction "OB1_2_31") (pintype "bidirectional"))
      (node (ref "IC1") (pin "32") (pinfunction "OB1_3_32") (pintype "bidirectional"))
      (node (ref "JP2") (pin "4") (pinfunction "4_4") (pintype "passive"))
    )
    (net (code "40") (name "Net-(IC1-OB2)") (class "Default")
      (node (ref "IC1") (pin "23") (pinfunction "OB2_23") (pintype "bidirectional"))
      (node (ref "IC1") (pin "24") (pinfunction "OB2_1_24") (pintype "bidirectional"))
      (node (ref "IC1") (pin "28") (pinfunction "OB2_2_28") (pintype "bidirectional"))
      (node (ref "IC1") (pin "29") (pinfunction "OB2_3_29") (pintype "bidirectional"))
      (node (ref "JP2") (pin "3") (pinfunction "3_3") (pintype "passive"))
    )
    (net (code "41") (name "Net-(IC1-SRA)") (class "Default")
      (node (ref "IC1") (pin "12") (pinfunction "SRA_12") (pintype "bidirectional"))
      (node (ref "R2") (pin "2") (pinfunction "2_2") (pintype "passive"))
    )
    (net (code "42") (name "Net-(IC1-SRB)") (class "Default")
      (node (ref "IC1") (pin "22") (pinfunction "SRB_22") (pintype "bidirectional"))
      (node (ref "R4") (pin "2") (pinfunction "2_2") (pintype "passive"))
    )
    (net (code "43") (name "Net-(IC1-VHS)") (class "Default")
      (node (ref "C11") (pin "1") (pinfunction "1_1") (pintype "passive"))
      (node (ref "IC1") (pin "35") (pinfunction "VHS_35") (pintype "bidirectional"))
    )
    (net (code "44") (name "Net-(IC2-5VOUT)") (class "Default")
      (node (ref "C19") (pin "1") (pinfunction "1_1") (pintype "passive"))
      (node (ref "IC2") (pin "13") (pinfunction "5VOUT_13") (pintype "bidirectional"))
    )
    (net (code "45") (name "Net-(IC2-BRA)") (class "Default")
      (node (ref "C21") (pin "1") (pinfunction "1_1") (pintype "passive"))
      (node (ref "IC2") (pin "9") (pinfunction "BRA_9") (pintype "bidirectional"))
      (node (ref "R10") (pin "1") (pinfunction "1_1") (pintype "passive"))
      (node (ref "R8") (pin "2") (pinfunction "2_2") (pintype "passive"))
    )
    (net (code "46") (name "Net-(IC2-BRB)") (class "Default")
      (node (ref "C22") (pin "1") (pinfunction "1_1") (pintype "passive"))
      (node (ref "IC2") (pin "25") (pinfunction "BRB_25") (pintype "bidirectional"))
      (node (ref "R7") (pin "2") (pinfunction "2_2") (pintype "passive"))
      (node (ref "R9") (pin "1") (pinfunction "1_1") (pintype "passive"))
    )
    (net (code "47") (name "Net-(IC2-OA1)") (class "Default")
      (node (ref "IC2") (pin "2") (pinfunction "OA1_2") (pintype "bidirectional"))
      (node (ref "IC2") (pin "3") (pinfunction "OA1_1_3") (pintype "bidirectional"))
      (node (ref "IC2") (pin "7") (pinfunction "OA1_2_7") (pintype "bidirectional"))
      (node (ref "IC2") (pin "8") (pinfunction "OA1_3_8") (pintype "bidirectional"))
      (node (ref "JP12") (pin "1") (pinfunction "1_1") (pintype "passive"))
    )
    (net (code "48") (name "Net-(IC2-OA2)") (class "Default")
      (node (ref "IC2") (pin "10") (pinfunction "OA2_2_10") (pintype "bidirectional"))
      (node (ref "IC2") (pin "11") (pinfunction "OA2_3_11") (pintype "bidirectional"))
      (node (ref "IC2") (pin "5") (pinfunction "OA2_5") (pintype "bidirectional"))
      (node (ref "IC2") (pin "6") (pinfunction "OA2_1_6") (pintype "bidirectional"))
      (node (ref "JP12") (pin "2") (pinfunction "2_2") (pintype "passive"))
    )
    (net (code "49") (name "Net-(IC2-OB1)") (class "Default")
      (node (ref "IC2") (pin "26") (pinfunction "OB1_26") (pintype "bidirectional"))
      (node (ref "IC2") (pin "27") (pinfunction "OB1_1_27") (pintype "bidirectional"))
      (node (ref "IC2") (pin "31") (pinfunction "OB1_2_31") (pintype "bidirectional"))
      (node (ref "IC2") (pin "32") (pinfunction "OB1_3_32") (pintype "bidirectional"))
      (node (ref "JP12") (pin "4") (pinfunction "4_4") (pintype "passive"))
    )
    (net (code "50") (name "Net-(IC2-OB2)") (class "Default")
      (node (ref "IC2") (pin "23") (pinfunction "OB2_23") (pintype "bidirectional"))
      (node (ref "IC2") (pin "24") (pinfunction "OB2_1_24") (pintype "bidirectional"))
      (node (ref "IC2") (pin "28") (pinfunction "OB2_2_28") (pintype "bidirectional"))
      (node (ref "IC2") (pin "29") (pinfunction "OB2_3_29") (pintype "bidirectional"))
      (node (ref "JP12") (pin "3") (pinfunction "3_3") (pintype "passive"))
    )
    (net (code "51") (name "Net-(IC2-SRA)") (class "Default")
      (node (ref "IC2") (pin "12") (pinfunction "SRA_12") (pintype "bidirectional"))
      (node (ref "R10") (pin "2") (pinfunction "2_2") (pintype "passive"))
    )
    (net (code "52") (name "Net-(IC2-SRB)") (class "Default")
      (node (ref "IC2") (pin "22") (pinfunction "SRB_22") (pintype "bidirectional"))
      (node (ref "R9") (pin "2") (pinfunction "2_2") (pintype "passive"))
    )
    (net (code "53") (name "Net-(IC2-VHS)") (class "Default")
      (node (ref "C15") (pin "1") (pinfunction "1_1") (pintype "passive"))
      (node (ref "IC2") (pin "35") (pinfunction "VHS_35") (pintype "bidirectional"))
    )
    (net (code "54") (name "Net-(IC4-5VOUT)") (class "Default")
      (node (ref "C41") (pin "1") (pinfunction "1_1") (pintype "passive"))
      (node (ref "IC4") (pin "13") (pinfunction "5VOUT_13") (pintype "bidirectional"))
    )
    (net (code "55") (name "Net-(IC4-BRA)") (class "Default")
      (node (ref "C43") (pin "1") (pinfunction "1_1") (pintype "passive"))
      (node (ref "IC4") (pin "9") (pinfunction "BRA_9") (pintype "bidirectional"))
      (node (ref "R18") (pin "2") (pinfunction "2_2") (pintype "passive"))
      (node (ref "R20") (pin "1") (pinfunction "1_1") (pintype "passive"))
    )
    (net (code "56") (name "Net-(IC4-BRB)") (class "Default")
      (node (ref "C44") (pin "1") (pinfunction "1_1") (pintype "passive"))
      (node (ref "IC4") (pin "25") (pinfunction "BRB_25") (pintype "bidirectional"))
      (node (ref "R17") (pin "2") (pinfunction "2_2") (pintype "passive"))
      (node (ref "R19") (pin "1") (pinfunction "1_1") (pintype "passive"))
    )
    (net (code "57") (name "Net-(IC4-OA1)") (class "Default")
      (node (ref "IC4") (pin "2") (pinfunction "OA1_2") (pintype "bidirectional"))
      (node (ref "IC4") (pin "3") (pinfunction "OA1_1_3") (pintype "bidirectional"))
      (node (ref "IC4") (pin "7") (pinfunction "OA1_2_7") (pintype "bidirectional"))
      (node (ref "IC4") (pin "8") (pinfunction "OA1_3_8") (pintype "bidirectional"))
      (node (ref "JP3") (pin "1") (pinfunction "1_1") (pintype "passive"))
    )
    (net (code "58") (name "Net-(IC4-OA2)") (class "Default")
      (node (ref "IC4") (pin "10") (pinfunction "OA2_2_10") (pintype "bidirectional"))
      (node (ref "IC4") (pin "11") (pinfunction "OA2_3_11") (pintype "bidirectional"))
      (node (ref "IC4") (pin "5") (pinfunction "OA2_5") (pintype "bidirectional"))
      (node (ref "IC4") (pin "6") (pinfunction "OA2_1_6") (pintype "bidirectional"))
      (node (ref "JP3") (pin "2") (pinfunction "2_2") (pintype "passive"))
    )
    (net (code "59") (name "Net-(IC4-OB1)") (class "Default")
      (node (ref "IC4") (pin "26") (pinfunction "OB1_26") (pintype "bidirectional"))
      (node (ref "IC4") (pin "27") (pinfunction "OB1_1_27") (pintype "bidirectional"))
      (node (ref "IC4") (pin "31") (pinfunction "OB1_2_31") (pintype "bidirectional"))
      (node (ref "IC4") (pin "32") (pinfunction "OB1_3_32") (pintype "bidirectional"))
      (node (ref "JP3") (pin "4") (pinfunction "4_4") (pintype "passive"))
    )
    (net (code "60") (name "Net-(IC4-OB2)") (class "Default")
      (node (ref "IC4") (pin "23") (pinfunction "OB2_23") (pintype "bidirectional"))
      (node (ref "IC4") (pin "24") (pinfunction "OB2_1_24") (pintype "bidirectional"))
      (node (ref "IC4") (pin "28") (pinfunction "OB2_2_28") (pintype "bidirectional"))
      (node (ref "IC4") (pin "29") (pinfunction "OB2_3_29") (pintype "bidirectional"))
      (node (ref "JP3") (pin "3") (pinfunction "3_3") (pintype "passive"))
    )
    (net (code "61") (name "Net-(IC4-SRA)") (class "Default")
      (node (ref "IC4") (pin "12") (pinfunction "SRA_12") (pintype "bidirectional"))
      (node (ref "R20") (pin "2") (pinfunction "2_2") (pintype "passive"))
    )
    (net (code "62") (name "Net-(IC4-SRB)") (class "Default")
      (node (ref "IC4") (pin "22") (pinfunction "SRB_22") (pintype "bidirectional"))
      (node (ref "R19") (pin "2") (pinfunction "2_2") (pintype "passive"))
    )
    (net (code "63") (name "Net-(IC4-VHS)") (class "Default")
      (node (ref "C37") (pin "1") (pinfunction "1_1") (pintype "passive"))
      (node (ref "IC4") (pin "35") (pinfunction "VHS_35") (pintype "bidirectional"))
    )
    (net (code "64") (name "Net-(PWR-PadA)") (class "Default")
      (node (ref "PWR") (pin "A") (pinfunction "A_A") (pintype "passive"))
      (node (ref "R30") (pin "2") (pinfunction "2_2") (pintype "passive"))
    )
    (net (code "65") (name "Net-(U$4-XI)") (class "Default")
      (node (ref "12MHZ") (pin "1") (pinfunction "1_1") (pintype "passive"))
      (node (ref "C28") (pin "2") (pinfunction "2_2") (pintype "passive"))
      (node (ref "U$4") (pin "7") (pinfunction "XI_7") (pintype "bidirectional"))
    )
    (net (code "66") (name "Net-(U$4-XO)") (class "Default")
      (node (ref "12MHZ") (pin "2") (pinfunction "2_2") (pintype "passive"))
      (node (ref "C29") (pin "2") (pinfunction "2_2") (pintype "passive"))
      (node (ref "U$4") (pin "8") (pinfunction "XO_8") (pintype "bidirectional"))
    )
    (net (code "67") (name "Net-(U1-PB6(XTAL1{slash}TOSC1))") (class "Default")
      (node (ref "C23") (pin "2") (pinfunction "2_2") (pintype "passive"))
      (node (ref "Q1") (pin "2") (pinfunction "2_2") (pintype "passive"))
      (node (ref "U1") (pin "7") (pinfunction "PB6(XTAL1/TOSC1)_7") (pintype "bidirectional"))
    )
    (net (code "68") (name "Net-(U1-PB7(XTAL2{slash}TOSC2))") (class "Default")
      (node (ref "C24") (pin "2") (pinfunction "2_2") (pintype "passive"))
      (node (ref "Q1") (pin "1") (pinfunction "1_1") (pintype "passive"))
      (node (ref "U1") (pin "8") (pinfunction "PB7(XTAL2/TOSC2)_8") (pintype "bidirectional"))
    )
    (net (code "69") (name "RESET_GRBL") (class "Default")
      (node (ref "C27") (pin "1") (pinfunction "1_1") (pintype "passive"))
      (node (ref "R11") (pin "1") (pinfunction "1_1") (pintype "passive"))
      (node (ref "S2") (pin "3") (pinfunction "3_3") (pintype "passive"))
      (node (ref "S2") (pin "4") (pinfunction "4_4") (pintype "passive"))
      (node (ref "U1") (pin "29") (pinfunction "PC6(/RESET)_29") (pintype "bidirectional"))
    )
    (net (code "70") (name "S1") (class "Default")
      (node (ref "U$3") (pin "S1") (pinfunction "S1_S1") (pintype "power_in"))
    )
    (net (code "71") (name "S2") (class "Default")
      (node (ref "U$3") (pin "S2") (pinfunction "S2_S2") (pintype "power_in"))
    )
    (net (code "72") (name "SCK") (class "Default")
      (node (ref "IC1") (pin "16") (pinfunction "SCK_16") (pintype "bidirectional"))
      (node (ref "IC2") (pin "16") (pinfunction "SCK_16") (pintype "bidirectional"))
      (node (ref "IC4") (pin "16") (pinfunction "SCK_16") (pintype "bidirectional"))
      (node (ref "U1") (pin "17") (pinfunction "PB5(SCK)_17") (pintype "bidirectional"))
    )
    (net (code "73") (name "SDO_X") (class "Default")
      (node (ref "IC2") (pin "14") (pinfunction "SDO_14") (pintype "bidirectional"))
      (node (ref "R3") (pin "1") (pinfunction "1_1") (pintype "passive"))
    )
    (net (code "74") (name "SDO_Y") (class "Default")
      (node (ref "IC1") (pin "14") (pinfunction "SDO_14") (pintype "bidirectional"))
      (node (ref "R1") (pin "1") (pinfunction "1_1") (pintype "passive"))
    )
    (net (code "75") (name "SDO_Z") (class "Default")
      (node (ref "IC4") (pin "14") (pinfunction "SDO_14") (pintype "bidirectional"))
      (node (ref "R16") (pin "1") (pinfunction "1_1") (pintype "passive"))
    )
    (net (code "76") (name "SPIN-PWM") (class "Default")
      (node (ref "JP8") (pin "2") (pinfunction "2_2") (pintype "passive"))
      (node (ref "U1") (pin "13") (pinfunction "PB1(OC1A)_13") (pintype "bidirectional"))
    )
    (net (code "77") (name "SPINDLE-DIR{slash}EN") (class "Default")
      (node (ref "JP8") (pin "1") (pinfunction "1_1") (pintype "passive"))
      (node (ref "U1") (pin "12") (pinfunction "PB0(ICP)_12") (pintype "bidirectional"))
    )
    (net (code "78") (name "STEP_X") (class "Default")
      (node (ref "IC1") (pin "42") (pinfunction "STEP_42") (pintype "bidirectional"))
      (node (ref "U1") (pin "32") (pinfunction "PD2(INT0)_32") (pintype "bidirectional"))
    )
    (net (code "79") (name "STEP_Y") (class "Default")
      (node (ref "IC2") (pin "42") (pinfunction "STEP_42") (pintype "bidirectional"))
      (node (ref "U1") (pin "1") (pinfunction "PD3(INT1)_1") (pintype "bidirectional"))
    )
    (net (code "80") (name "STEP_Z") (class "Default")
      (node (ref "IC4") (pin "42") (pinfunction "STEP_42") (pintype "bidirectional"))
      (node (ref "U1") (pin "2") (pinfunction "PD4(XCK/T0)_2") (pintype "bidirectional"))
    )
    (net (code "81") (name "V+") (class "Default")
      (node (ref "C52") (pin "+") (pinfunction "+_+") (pintype "passive"))
      (node (ref "F1") (pin "P$2") (pinfunction "2_P$2") (pintype "passive"))
      (node (ref "F2") (pin "P$2") (pinfunction "2_P$2") (pintype "passive"))
      (node (ref "F4") (pin "P$2") (pinfunction "2_P$2") (pintype "passive"))
      (node (ref "IC3") (pin "1") (pinfunction "IN_1") (pintype "input"))
      (node (ref "JP6") (pin "1") (pinfunction "1_1") (pintype "passive"))
      (node (ref "ZN1") (pin "P$1") (pinfunction "C_P$1") (pintype "passive"))
    )
    (net (code "82") (name "VCC") (class "Default")
      (node (ref "C25") (pin "2") (pinfunction "2_2") (pintype "passive"))
      (node (ref "C26") (pin "+") (pinfunction "+_+") (pintype "passive"))
      (node (ref "C31") (pin "2") (pinfunction "2_2") (pintype "passive"))
      (node (ref "C53") (pin "+") (pinfunction "+_+") (pintype "passive"))
      (node (ref "IC3") (pin "4") (pinfunction "FB_4") (pintype "input"))
      (node (ref "L1") (pin "2") (pinfunction "2_2") (pintype "passive"))
      (node (ref "R11") (pin "2") (pinfunction "2_2") (pintype "passive"))
      (node (ref "R12") (pin "1") (pinfunction "1_1") (pintype "passive"))
      (node (ref "R13") (pin "1") (pinfunction "1_1") (pintype "passive"))
      (node (ref "R15") (pin "1") (pinfunction "1_1") (pintype "passive"))
      (node (ref "R30") (pin "1") (pinfunction "1_1") (pintype "passive"))
      (node (ref "U$4") (pin "16") (pinfunction "VCC_16") (pintype "bidirectional"))
      (node (ref "U1") (pin "18") (pinfunction "AVCC_18") (pintype "bidirectional"))
      (node (ref "U1") (pin "4") (pinfunction "VCC_4") (pintype "bidirectional"))
      (node (ref "U1") (pin "6") (pinfunction "VCC_6") (pintype "bidirectional"))
    )
    (net (code "83") (name "X-END") (class "Default")
      (node (ref "D2") (pin "A") (pinfunction "A_A") (pintype "passive"))
      (node (ref "R12") (pin "2") (pinfunction "2_2") (pintype "passive"))
      (node (ref "U1") (pin "26") (pinfunction "PC3(ADC3)_26") (pintype "bidirectional"))
    )
    (net (code "84") (name "Y-END") (class "Default")
      (node (ref "D3") (pin "A") (pinfunction "A_A") (pintype "passive"))
      (node (ref "R13") (pin "2") (pinfunction "2_2") (pintype "passive"))
      (node (ref "U1") (pin "27") (pinfunction "PC4(ADC4/SDA)_27") (pintype "bidirectional"))
    )
    (net (code "85") (name "Z-END") (class "Default")
      (node (ref "D5") (pin "A") (pinfunction "A_A") (pintype "passive"))
      (node (ref "R15") (pin "2") (pinfunction "2_2") (pintype "passive"))
      (node (ref "U1") (pin "28") (pinfunction "PC5(ADC5/SCL)_28") (pintype "bidirectional"))
    )
    (net (code "86") (name "unconnected-(IC1-OSC-Pad21)") (class "Default")
      (node (ref "IC1") (pin "21") (pinfunction "OSC_21") (pintype "bidirectional"))
    )
    (net (code "87") (name "unconnected-(IC1-SIG_TST-Pad38)") (class "Default")
      (node (ref "IC1") (pin "38") (pinfunction "SIG_TST_38") (pintype "bidirectional"))
    )
    (net (code "88") (name "unconnected-(IC1-TEST_ANA-Pad37)") (class "Default")
      (node (ref "IC1") (pin "37") (pinfunction "TEST_ANA_37") (pintype "bidirectional"))
    )
    (net (code "89") (name "unconnected-(IC2-OSC-Pad21)") (class "Default")
      (node (ref "IC2") (pin "21") (pinfunction "OSC_21") (pintype "bidirectional"))
    )
    (net (code "90") (name "unconnected-(IC2-SIG_TST-Pad38)") (class "Default")
      (node (ref "IC2") (pin "38") (pinfunction "SIG_TST_38") (pintype "bidirectional"))
    )
    (net (code "91") (name "unconnected-(IC2-TEST_ANA-Pad37)") (class "Default")
      (node (ref "IC2") (pin "37") (pinfunction "TEST_ANA_37") (pintype "bidirectional"))
    )
    (net (code "92") (name "unconnected-(IC4-OSC-Pad21)") (class "Default")
      (node (ref "IC4") (pin "21") (pinfunction "OSC_21") (pintype "bidirectional"))
    )
    (net (code "93") (name "unconnected-(IC4-SIG_TST-Pad38)") (class "Default")
      (node (ref "IC4") (pin "38") (pinfunction "SIG_TST_38") (pintype "bidirectional"))
    )
    (net (code "94") (name "unconnected-(IC4-TEST_ANA-Pad37)") (class "Default")
      (node (ref "IC4") (pin "37") (pinfunction "TEST_ANA_37") (pintype "bidirectional"))
    )
    (net (code "95") (name "unconnected-(JP5-PadVBUS)") (class "Default")
      (node (ref "JP5") (pin "VBUS") (pinfunction "VBUS_VBUS") (pintype "bidirectional"))
    )
    (net (code "96") (name "unconnected-(U$4-CTS-Pad9)") (class "Default")
      (node (ref "U$4") (pin "9") (pinfunction "CTS_9") (pintype "bidirectional"))
    )
    (net (code "97") (name "unconnected-(U$4-DCD-Pad12)") (class "Default")
      (node (ref "U$4") (pin "12") (pinfunction "DCD_12") (pintype "bidirectional"))
    )
    (net (code "98") (name "unconnected-(U$4-DSR-Pad10)") (class "Default")
      (node (ref "U$4") (pin "10") (pinfunction "DSR_10") (pintype "bidirectional"))
    )
    (net (code "99") (name "unconnected-(U$4-RI-Pad11)") (class "Default")
      (node (ref "U$4") (pin "11") (pinfunction "RI_11") (pintype "bidirectional"))
    )
    (net (code "100") (name "unconnected-(U$4-RS232-Pad15)") (class "Default")
      (node (ref "U$4") (pin "15") (pinfunction "RS232_15") (pintype "bidirectional"))
    )
    (net (code "101") (name "unconnected-(U$4-RTS-Pad14)") (class "Default")
      (node (ref "U$4") (pin "14") (pinfunction "RTS_14") (pintype "bidirectional"))
    )
    (net (code "102") (name "unconnected-(U1-ADC6-Pad19)") (class "Default")
      (node (ref "U1") (pin "19") (pinfunction "ADC6_19") (pintype "bidirectional"))
    )
    (net (code "103") (name "unconnected-(U1-ADC7-Pad22)") (class "Default")
      (node (ref "U1") (pin "22") (pinfunction "ADC7_22") (pintype "bidirectional"))
    )
    (net (code "104") (name "unconnected-(U1-AREF-Pad20)") (class "Default")
      (node (ref "U1") (pin "20") (pinfunction "AREF_20") (pintype "bidirectional"))
    )
  )
)
